# mux.net
KiCad netlist of a schematic drawn in Altium Designer
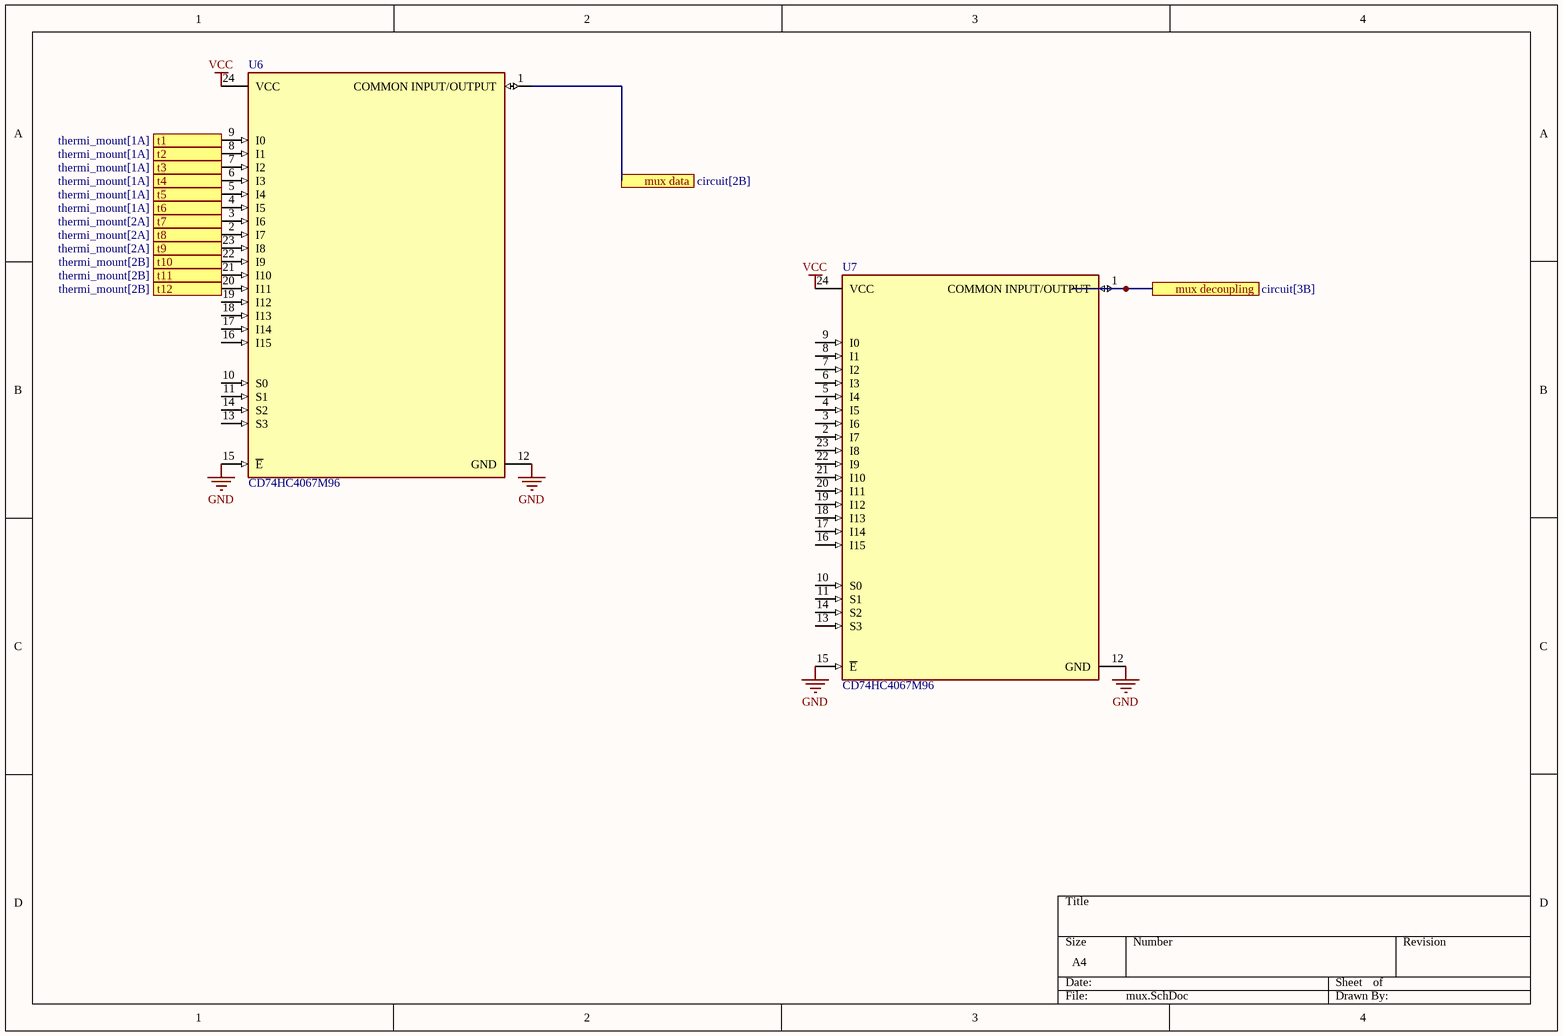
[diagram p0: mux.SchDoc]

(export (version "E")
  (design (tool "Eeschema 10.0.6"))
  (components
    (comp (ref "U6")
      (value "CD74HC4067M96")
      (footprint "FP-DW0024A-MFG")
      (description "IC MUX/DEMUX 1X16 24SOIC")
      (fields
        (field (name "OCTOPART") "https://octopart.com/cd74hc4067m96-texas+instruments-722802")
        (field (name "MANUFACTURER") "Texas Instruments")
      )
      (libsource (lib "Altium Content Vault") (part "0e3014a41e7f600214dac1b4fa06845"))
    )
    (comp (ref "U7")
      (value "CD74HC4067M96")
      (footprint "FP-DW0024A-MFG")
      (description "IC MUX/DEMUX 1X16 24SOIC")
      (fields
        (field (name "OCTOPART") "https://octopart.com/cd74hc4067m96-texas+instruments-722802")
        (field (name "MANUFACTURER") "Texas Instruments")
      )
      (libsource (lib "Altium Content Vault") (part "0e3014a41e7f600214dac1b4fa06845"))
    )
  )
  (nets
    (net (code "1") (name "/mux data") (class "Default")
      (node (ref "U6") (pin "1") (pinfunction "COMMON_INPUT/OUTPUT_1") (pintype "bidirectional"))
    )
    (net (code "2") (name "/mux decoupling") (class "Default")
      (node (ref "U7") (pin "1") (pinfunction "COMMON_INPUT/OUTPUT_1") (pintype "bidirectional"))
    )
    (net (code "3") (name "/t1") (class "Default")
      (node (ref "U6") (pin "9") (pinfunction "I0_9") (pintype "input"))
    )
    (net (code "4") (name "/t2") (class "Default")
      (node (ref "U6") (pin "8") (pinfunction "I1_8") (pintype "input"))
    )
    (net (code "5") (name "/t3") (class "Default")
      (node (ref "U6") (pin "7") (pinfunction "I2_7") (pintype "input"))
    )
    (net (code "6") (name "/t4") (class "Default")
      (node (ref "U6") (pin "6") (pinfunction "I3_6") (pintype "input"))
    )
    (net (code "7") (name "/t5") (class "Default")
      (node (ref "U6") (pin "5") (pinfunction "I4_5") (pintype "input"))
    )
    (net (code "8") (name "/t6") (class "Default")
      (node (ref "U6") (pin "4") (pinfunction "I5_4") (pintype "input"))
    )
    (net (code "9") (name "/t7") (class "Default")
      (node (ref "U6") (pin "3") (pinfunction "I6_3") (pintype "input"))
    )
    (net (code "10") (name "/t8") (class "Default")
      (node (ref "U6") (pin "2") (pinfunction "I7_2") (pintype "input"))
    )
    (net (code "11") (name "/t9") (class "Default")
      (node (ref "U6") (pin "23") (pinfunction "I8_23") (pintype "input"))
    )
    (net (code "12") (name "/t10") (class "Default")
      (node (ref "U6") (pin "22") (pinfunction "I9_22") (pintype "input"))
    )
    (net (code "13") (name "/t11") (class "Default")
      (node (ref "U6") (pin "21") (pinfunction "I10_21") (pintype "input"))
    )
    (net (code "14") (name "/t12") (class "Default")
      (node (ref "U6") (pin "20") (pinfunction "I11_20") (pintype "input"))
    )
    (net (code "15") (name "GND") (class "Default")
      (node (ref "U6") (pin "12") (pinfunction "GND_12") (pintype "power_in"))
      (node (ref "U6") (pin "15") (pinfunction "~{E}_15") (pintype "input"))
      (node (ref "U7") (pin "12") (pinfunction "GND_12") (pintype "power_in"))
      (node (ref "U7") (pin "15") (pinfunction "~{E}_15") (pintype "input"))
    )
    (net (code "16") (name "VCC") (class "Default")
      (node (ref "U6") (pin "24") (pinfunction "VCC_24") (pintype "power_in"))
      (node (ref "U7") (pin "24") (pinfunction "VCC_24") (pintype "power_in"))
    )
    (net (code "17") (name "unconnected-(U6-I12-Pad19)") (class "Default")
      (node (ref "U6") (pin "19") (pinfunction "I12_19") (pintype "input"))
    )
    (net (code "18") (name "unconnected-(U6-I13-Pad18)") (class "Default")
      (node (ref "U6") (pin "18") (pinfunction "I13_18") (pintype "input"))
    )
    (net (code "19") (name "unconnected-(U6-I14-Pad17)") (class "Default")
      (node (ref "U6") (pin "17") (pinfunction "I14_17") (pintype "input"))
    )
    (net (code "20") (name "unconnected-(U6-I15-Pad16)") (class "Default")
      (node (ref "U6") (pin "16") (pinfunction "I15_16") (pintype "input"))
    )
    (net (code "21") (name "unconnected-(U6-S0-Pad10)") (class "Default")
      (node (ref "U6") (pin "10") (pinfunction "S0_10") (pintype "input"))
    )
    (net (code "22") (name "unconnected-(U6-S1-Pad11)") (class "Default")
      (node (ref "U6") (pin "11") (pinfunction "S1_11") (pintype "input"))
    )
    (net (code "23") (name "unconnected-(U6-S2-Pad14)") (class "Default")
      (node (ref "U6") (pin "14") (pinfunction "S2_14") (pintype "input"))
    )
    (net (code "24") (name "unconnected-(U6-S3-Pad13)") (class "Default")
      (node (ref "U6") (pin "13") (pinfunction "S3_13") (pintype "input"))
    )
    (net (code "25") (name "unconnected-(U7-I0-Pad9)") (class "Default")
      (node (ref "U7") (pin "9") (pinfunction "I0_9") (pintype "input"))
    )
    (net (code "26") (name "unconnected-(U7-I1-Pad8)") (class "Default")
      (node (ref "U7") (pin "8") (pinfunction "I1_8") (pintype "input"))
    )
    (net (code "27") (name "unconnected-(U7-I2-Pad7)") (class "Default")
      (node (ref "U7") (pin "7") (pinfunction "I2_7") (pintype "input"))
    )
    (net (code "28") (name "unconnected-(U7-I3-Pad6)") (class "Default")
      (node (ref "U7") (pin "6") (pinfunction "I3_6") (pintype "input"))
    )
    (net (code "29") (name "unconnected-(U7-I4-Pad5)") (class "Default")
      (node (ref "U7") (pin "5") (pinfunction "I4_5") (pintype "input"))
    )
    (net (code "30") (name "unconnected-(U7-I5-Pad4)") (class "Default")
      (node (ref "U7") (pin "4") (pinfunction "I5_4") (pintype "input"))
    )
    (net (code "31") (name "unconnected-(U7-I6-Pad3)") (class "Default")
      (node (ref "U7") (pin "3") (pinfunction "I6_3") (pintype "input"))
    )
    (net (code "32") (name "unconnected-(U7-I7-Pad2)") (class "Default")
      (node (ref "U7") (pin "2") (pinfunction "I7_2") (pintype "input"))
    )
    (net (code "33") (name "unconnected-(U7-I8-Pad23)") (class "Default")
      (node (ref "U7") (pin "23") (pinfunction "I8_23") (pintype "input"))
    )
    (net (code "34") (name "unconnected-(U7-I9-Pad22)") (class "Default")
      (node (ref "U7") (pin "22") (pinfunction "I9_22") (pintype "input"))
    )
    (net (code "35") (name "unconnected-(U7-I10-Pad21)") (class "Default")
      (node (ref "U7") (pin "21") (pinfunction "I10_21") (pintype "input"))
    )
    (net (code "36") (name "unconnected-(U7-I11-Pad20)") (class "Default")
      (node (ref "U7") (pin "20") (pinfunction "I11_20") (pintype "input"))
    )
    (net (code "37") (name "unconnected-(U7-I12-Pad19)") (class "Default")
      (node (ref "U7") (pin "19") (pinfunction "I12_19") (pintype "input"))
    )
    (net (code "38") (name "unconnected-(U7-I13-Pad18)") (class "Default")
      (node (ref "U7") (pin "18") (pinfunction "I13_18") (pintype "input"))
    )
    (net (code "39") (name "unconnected-(U7-I14-Pad17)") (class "Default")
      (node (ref "U7") (pin "17") (pinfunction "I14_17") (pintype "input"))
    )
    (net (code "40") (name "unconnected-(U7-I15-Pad16)") (class "Default")
      (node (ref "U7") (pin "16") (pinfunction "I15_16") (pintype "input"))
    )
    (net (code "41") (name "unconnected-(U7-S0-Pad10)") (class "Default")
      (node (ref "U7") (pin "10") (pinfunction "S0_10") (pintype "input"))
    )
    (net (code "42") (name "unconnected-(U7-S1-Pad11)") (class "Default")
      (node (ref "U7") (pin "11") (pinfunction "S1_11") (pintype "input"))
    )
    (net (code "43") (name "unconnected-(U7-S2-Pad14)") (class "Default")
      (node (ref "U7") (pin "14") (pinfunction "S2_14") (pintype "input"))
    )
    (net (code "44") (name "unconnected-(U7-S3-Pad13)") (class "Default")
      (node (ref "U7") (pin "13") (pinfunction "S3_13") (pintype "input"))
    )
  )
)
